# RlyCtrl.net
KiCad netlist of a schematic drawn in Altium Designer
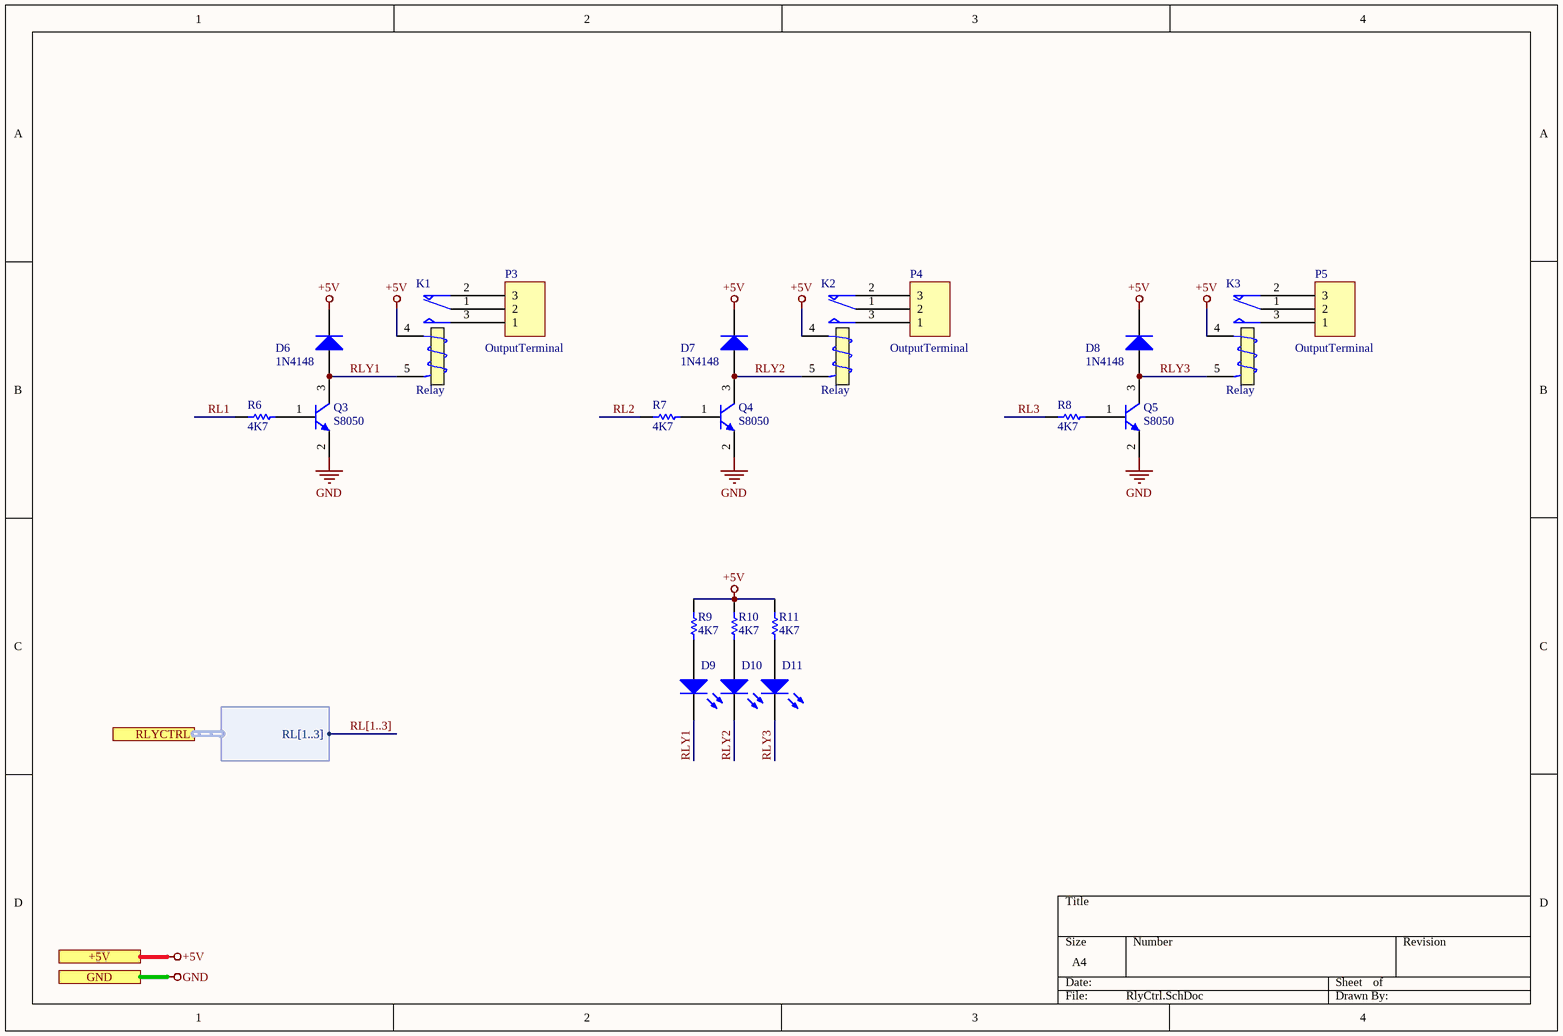
[diagram p0: RlyCtrl.SchDoc]

(export (version "E")
  (design (tool "Eeschema 10.0.6"))
  (components
    (comp (ref "D6")
      (value "1N4148")
      (footprint "D-SOD-80")
      (description "1 Amp General Purpose Rectifier")
      (libsource (lib "Miscellaneous Devices") (part "Diode 1N4004"))
    )
    (comp (ref "D7")
      (value "1N4148")
      (footprint "D-SOD-80")
      (description "1 Amp General Purpose Rectifier")
      (libsource (lib "Miscellaneous Devices") (part "Diode 1N4004"))
    )
    (comp (ref "D8")
      (value "1N4148")
      (footprint "D-SOD-80")
      (description "1 Amp General Purpose Rectifier")
      (libsource (lib "Miscellaneous Devices") (part "Diode 1N4004"))
    )
    (comp (ref "D9")
      (value "SMD0805-RED")
      (footprint "LED-0805")
      (description "Typical INFRARED GaAs LED")
      (libsource (lib "Miscellaneous Devices") (part "LED0"))
    )
    (comp (ref "D10")
      (value "SMD0805-RED")
      (footprint "LED-0805")
      (description "Typical INFRARED GaAs LED")
      (libsource (lib "Miscellaneous Devices") (part "LED0"))
    )
    (comp (ref "D11")
      (value "SMD0805-RED")
      (footprint "LED-0805")
      (description "Typical INFRARED GaAs LED")
      (libsource (lib "Miscellaneous Devices") (part "LED0"))
    )
    (comp (ref "K1")
      (value "Relay")
      (footprint "MODULE5B")
      (description "SPDT Relay")
      (fields (field (name "PUBLISHER") "Altium Limited"))
      (libsource (lib "Miscellaneous Devices") (part "Relay"))
    )
    (comp (ref "K2")
      (value "Relay")
      (footprint "MODULE5B")
      (description "SPDT Relay")
      (fields (field (name "PUBLISHER") "Altium Limited"))
      (libsource (lib "Miscellaneous Devices") (part "Relay"))
    )
    (comp (ref "K3")
      (value "Relay")
      (footprint "MODULE5B")
      (description "SPDT Relay")
      (fields (field (name "PUBLISHER") "Altium Limited"))
      (libsource (lib "Miscellaneous Devices") (part "Relay"))
    )
    (comp (ref "P3")
      (value "OutputTerminal")
      (footprint "TER-KF128-3P")
      (description "Header, 3-Pin")
      (fields (field (name "Comment") "KF128-3P"))
      (libsource (lib "Miscellaneous Connectors") (part "Header 3"))
    )
    (comp (ref "P4")
      (value "OutputTerminal")
      (footprint "TER-KF128-3P")
      (description "Header, 3-Pin")
      (fields (field (name "Comment") "KF128-3P"))
      (libsource (lib "Miscellaneous Connectors") (part "Header 3"))
    )
    (comp (ref "P5")
      (value "OutputTerminal")
      (footprint "TER-KF128-3P")
      (description "Header, 3-Pin")
      (fields (field (name "Comment") "KF128-3P"))
      (libsource (lib "Miscellaneous Connectors") (part "Header 3"))
    )
    (comp (ref "Q3")
      (value "S8050")
      (footprint "TO-226-AA")
      (description "NPN Bipolar Transistor")
      (fields (field (name "MANUFACTURER") "MCC") (field (name "MANUFACTURER PART NUMBER") "MMSS8050-H-TP"))
      (libsource (lib "Miscellaneous Devices") (part "NPN"))
    )
    (comp (ref "Q4")
      (value "S8050")
      (footprint "TO-226-AA")
      (description "NPN Bipolar Transistor")
      (fields (field (name "MANUFACTURER") "MCC") (field (name "MANUFACTURER PART NUMBER") "MMSS8050-H-TP"))
      (libsource (lib "Miscellaneous Devices") (part "NPN"))
    )
    (comp (ref "Q5")
      (value "S8050")
      (footprint "TO-226-AA")
      (description "NPN Bipolar Transistor")
      (fields (field (name "MANUFACTURER") "MCC") (field (name "MANUFACTURER PART NUMBER") "MMSS8050-H-TP"))
      (libsource (lib "Miscellaneous Devices") (part "NPN"))
    )
    (comp (ref "R6")
      (value "4K7")
      (footprint "AXIAL-0.3")
      (description "Resistor")
      (libsource (lib "Miscellaneous Devices") (part "Res1"))
    )
    (comp (ref "R7")
      (value "4K7")
      (footprint "AXIAL-0.3")
      (description "Resistor")
      (libsource (lib "Miscellaneous Devices") (part "Res1"))
    )
    (comp (ref "R8")
      (value "4K7")
      (footprint "AXIAL-0.3")
      (description "Resistor")
      (libsource (lib "Miscellaneous Devices") (part "Res1"))
    )
    (comp (ref "R9")
      (value "4K7")
      (footprint "R-0805")
      (description "Resistor")
      (fields (field (name "PUBLISHER") "Altium Limited"))
      (libsource (lib "Miscellaneous Devices") (part "Res1"))
    )
    (comp (ref "R10")
      (value "4K7")
      (footprint "R-0805")
      (description "Resistor")
      (fields (field (name "PUBLISHER") "Altium Limited"))
      (libsource (lib "Miscellaneous Devices") (part "Res1"))
    )
    (comp (ref "R11")
      (value "4K7")
      (footprint "R-0805")
      (description "Resistor")
      (fields (field (name "PUBLISHER") "Altium Limited"))
      (libsource (lib "Miscellaneous Devices") (part "Res1"))
    )
  )
  (nets
    (net (code "2") (name "+5V") (class "Default")
      (node (ref "D6") (pin "2") (pinfunction "K_2") (pintype "passive"))
      (node (ref "D7") (pin "2") (pinfunction "K_2") (pintype "passive"))
      (node (ref "D8") (pin "2") (pinfunction "K_2") (pintype "passive"))
      (node (ref "K1") (pin "4") (pinfunction "T1_4") (pintype "passive"))
      (node (ref "K2") (pin "4") (pinfunction "T1_4") (pintype "passive"))
      (node (ref "K3") (pin "4") (pinfunction "T1_4") (pintype "passive"))
      (node (ref "R10") (pin "2") (pinfunction "2_2") (pintype "passive"))
      (node (ref "R11") (pin "2") (pinfunction "2_2") (pintype "passive"))
      (node (ref "R9") (pin "2") (pinfunction "2_2") (pintype "passive"))
    )
    (net (code "3") (name "/RL1") (class "Default")
      (node (ref "R6") (pin "2") (pinfunction "2_2") (pintype "passive"))
    )
    (net (code "4") (name "/RL2") (class "Default")
      (node (ref "R7") (pin "2") (pinfunction "2_2") (pintype "passive"))
    )
    (net (code "5") (name "/RL3") (class "Default")
      (node (ref "R8") (pin "2") (pinfunction "2_2") (pintype "passive"))
    )
    (net (code "6") (name "/RLY1") (class "Default")
      (node (ref "D6") (pin "1") (pinfunction "A_1") (pintype "passive"))
      (node (ref "D9") (pin "2") (pinfunction "K_2") (pintype "passive"))
      (node (ref "K1") (pin "5") (pinfunction "T2_5") (pintype "passive"))
      (node (ref "Q3") (pin "3") (pinfunction "C_3") (pintype "passive"))
    )
    (net (code "7") (name "/RLY2") (class "Default")
      (node (ref "D10") (pin "2") (pinfunction "K_2") (pintype "passive"))
      (node (ref "D7") (pin "1") (pinfunction "A_1") (pintype "passive"))
      (node (ref "K2") (pin "5") (pinfunction "T2_5") (pintype "passive"))
      (node (ref "Q4") (pin "3") (pinfunction "C_3") (pintype "passive"))
    )
    (net (code "8") (name "/RLY3") (class "Default")
      (node (ref "D11") (pin "2") (pinfunction "K_2") (pintype "passive"))
      (node (ref "D8") (pin "1") (pinfunction "A_1") (pintype "passive"))
      (node (ref "K3") (pin "5") (pinfunction "T2_5") (pintype "passive"))
      (node (ref "Q5") (pin "3") (pinfunction "C_3") (pintype "passive"))
    )
    (net (code "11") (name "GND") (class "Default")
      (node (ref "Q3") (pin "2") (pinfunction "E_2") (pintype "passive"))
      (node (ref "Q4") (pin "2") (pinfunction "E_2") (pintype "passive"))
      (node (ref "Q5") (pin "2") (pinfunction "E_2") (pintype "passive"))
    )
    (net (code "12") (name "Net-(D9-A)") (class "Default")
      (node (ref "D9") (pin "1") (pinfunction "A_1") (pintype "passive"))
      (node (ref "R9") (pin "1") (pinfunction "1_1") (pintype "passive"))
    )
    (net (code "13") (name "Net-(D10-A)") (class "Default")
      (node (ref "D10") (pin "1") (pinfunction "A_1") (pintype "passive"))
      (node (ref "R10") (pin "1") (pinfunction "1_1") (pintype "passive"))
    )
    (net (code "14") (name "Net-(D11-A)") (class "Default")
      (node (ref "D11") (pin "1") (pinfunction "A_1") (pintype "passive"))
      (node (ref "R11") (pin "1") (pinfunction "1_1") (pintype "passive"))
    )
    (net (code "15") (name "Net-(K1-COM)") (class "Default")
      (node (ref "K1") (pin "1") (pinfunction "COM_1") (pintype "passive"))
      (node (ref "P3") (pin "2") (pinfunction "2_2") (pintype "passive"))
    )
    (net (code "16") (name "Net-(K1-NC)") (class "Default")
      (node (ref "K1") (pin "2") (pinfunction "NC_2") (pintype "passive"))
      (node (ref "P3") (pin "3") (pinfunction "3_3") (pintype "passive"))
    )
    (net (code "17") (name "Net-(K1-NO)") (class "Default")
      (node (ref "K1") (pin "3") (pinfunction "NO_3") (pintype "passive"))
      (node (ref "P3") (pin "1") (pinfunction "1_1") (pintype "passive"))
    )
    (net (code "18") (name "Net-(K2-COM)") (class "Default")
      (node (ref "K2") (pin "1") (pinfunction "COM_1") (pintype "passive"))
      (node (ref "P4") (pin "2") (pinfunction "2_2") (pintype "passive"))
    )
    (net (code "19") (name "Net-(K2-NC)") (class "Default")
      (node (ref "K2") (pin "2") (pinfunction "NC_2") (pintype "passive"))
      (node (ref "P4") (pin "3") (pinfunction "3_3") (pintype "passive"))
    )
    (net (code "20") (name "Net-(K2-NO)") (class "Default")
      (node (ref "K2") (pin "3") (pinfunction "NO_3") (pintype "passive"))
      (node (ref "P4") (pin "1") (pinfunction "1_1") (pintype "passive"))
    )
    (net (code "21") (name "Net-(K3-COM)") (class "Default")
      (node (ref "K3") (pin "1") (pinfunction "COM_1") (pintype "passive"))
      (node (ref "P5") (pin "2") (pinfunction "2_2") (pintype "passive"))
    )
    (net (code "22") (name "Net-(K3-NC)") (class "Default")
      (node (ref "K3") (pin "2") (pinfunction "NC_2") (pintype "passive"))
      (node (ref "P5") (pin "3") (pinfunction "3_3") (pintype "passive"))
    )
    (net (code "23") (name "Net-(K3-NO)") (class "Default")
      (node (ref "K3") (pin "3") (pinfunction "NO_3") (pintype "passive"))
      (node (ref "P5") (pin "1") (pinfunction "1_1") (pintype "passive"))
    )
    (net (code "24") (name "Net-(Q3-B)") (class "Default")
      (node (ref "Q3") (pin "1") (pinfunction "B_1") (pintype "passive"))
      (node (ref "R6") (pin "1") (pinfunction "1_1") (pintype "passive"))
    )
    (net (code "25") (name "Net-(Q4-B)") (class "Default")
      (node (ref "Q4") (pin "1") (pinfunction "B_1") (pintype "passive"))
      (node (ref "R7") (pin "1") (pinfunction "1_1") (pintype "passive"))
    )
    (net (code "26") (name "Net-(Q5-B)") (class "Default")
      (node (ref "Q5") (pin "1") (pinfunction "B_1") (pintype "passive"))
      (node (ref "R8") (pin "1") (pinfunction "1_1") (pintype "passive"))
    )
  )
)
